# GR_Screen.net
KiCad netlist of a schematic drawn in Altium Designer
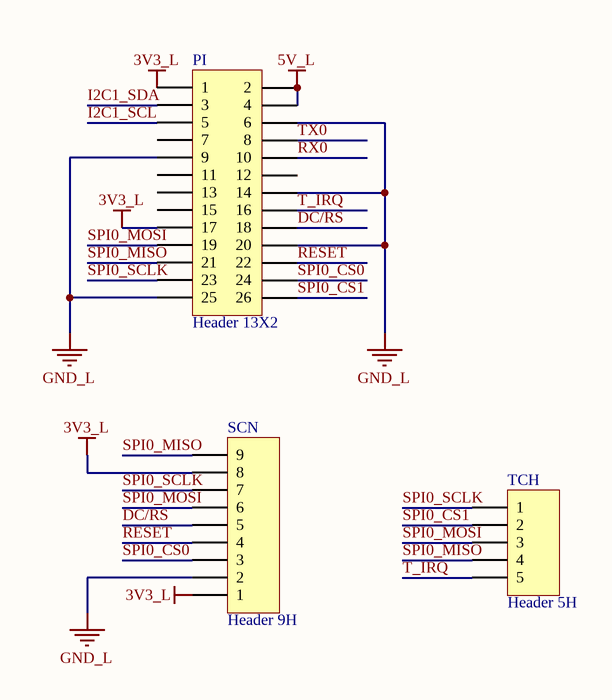
[diagram p0: GR_Screen.SchDoc]

(export (version "E")
  (design (tool "Eeschema 10.0.6"))
  (components
    (comp (ref "PI")
      (value "Header 13X2")
      (footprint "HDR2X13")
      (description "Header, 13-Pin, Dual row")
      (fields (field (name "PUBLISHER") "Altium Limited"))
      (libsource (lib "Miscellaneous Connectors") (part "Header 13X2"))
    )
    (comp (ref "SCN")
      (value "Header 9H")
      (footprint "MOLEX SPOX 9H")
      (description "Header, 9-Pin, Right Angle")
      (fields (field (name "PUBLISHER") "Altium Limited"))
      (libsource (lib "Miscellaneous Connectors") (part "Header 9H"))
    )
    (comp (ref "TCH")
      (value "Header 5H")
      (footprint "MOLEX SPOX 5H")
      (description "Header, 5-Pin, Right Angle")
      (fields (field (name "PUBLISHER") "Altium Limited"))
      (libsource (lib "Miscellaneous Connectors") (part "Header 5H"))
    )
  )
  (nets
    (net (code "1") (name "/DC{slash}RS") (class "Default")
      (node (ref "PI") (pin "18") (pinfunction "18_18") (pintype "passive"))
      (node (ref "SCN") (pin "5") (pinfunction "5_5") (pintype "passive"))
    )
    (net (code "2") (name "/I2C1_SCL") (class "Default")
      (node (ref "PI") (pin "5") (pinfunction "5_5") (pintype "passive"))
    )
    (net (code "3") (name "/I2C1_SDA") (class "Default")
      (node (ref "PI") (pin "3") (pinfunction "3_3") (pintype "passive"))
    )
    (net (code "4") (name "/RESET") (class "Default")
      (node (ref "PI") (pin "22") (pinfunction "22_22") (pintype "passive"))
      (node (ref "SCN") (pin "4") (pinfunction "4_4") (pintype "passive"))
    )
    (net (code "5") (name "/RX0") (class "Default")
      (node (ref "PI") (pin "10") (pinfunction "10_10") (pintype "passive"))
    )
    (net (code "6") (name "/SPI0_CS0") (class "Default")
      (node (ref "PI") (pin "24") (pinfunction "24_24") (pintype "passive"))
      (node (ref "SCN") (pin "3") (pinfunction "3_3") (pintype "passive"))
    )
    (net (code "7") (name "/SPI0_CS1") (class "Default")
      (node (ref "PI") (pin "26") (pinfunction "26_26") (pintype "passive"))
      (node (ref "TCH") (pin "2") (pinfunction "2_2") (pintype "passive"))
    )
    (net (code "8") (name "/SPI0_MISO") (class "Default")
      (node (ref "PI") (pin "21") (pinfunction "21_21") (pintype "passive"))
      (node (ref "SCN") (pin "9") (pinfunction "9_9") (pintype "passive"))
      (node (ref "TCH") (pin "4") (pinfunction "4_4") (pintype "passive"))
    )
    (net (code "9") (name "/SPI0_MOSI") (class "Default")
      (node (ref "PI") (pin "19") (pinfunction "19_19") (pintype "passive"))
      (node (ref "SCN") (pin "6") (pinfunction "6_6") (pintype "passive"))
      (node (ref "TCH") (pin "3") (pinfunction "3_3") (pintype "passive"))
    )
    (net (code "10") (name "/SPI0_SCLK") (class "Default")
      (node (ref "PI") (pin "23") (pinfunction "23_23") (pintype "passive"))
      (node (ref "SCN") (pin "7") (pinfunction "7_7") (pintype "passive"))
      (node (ref "TCH") (pin "1") (pinfunction "1_1") (pintype "passive"))
    )
    (net (code "11") (name "/TX0") (class "Default")
      (node (ref "PI") (pin "8") (pinfunction "8_8") (pintype "passive"))
    )
    (net (code "12") (name "/T_IRQ") (class "Default")
      (node (ref "PI") (pin "16") (pinfunction "16_16") (pintype "passive"))
      (node (ref "TCH") (pin "5") (pinfunction "5_5") (pintype "passive"))
    )
    (net (code "13") (name "3V3_L") (class "Default")
      (node (ref "PI") (pin "1") (pinfunction "1_1") (pintype "passive"))
      (node (ref "PI") (pin "17") (pinfunction "17_17") (pintype "passive"))
      (node (ref "SCN") (pin "1") (pinfunction "1_1") (pintype "passive"))
      (node (ref "SCN") (pin "8") (pinfunction "8_8") (pintype "passive"))
    )
    (net (code "14") (name "5V_L") (class "Default")
      (node (ref "PI") (pin "2") (pinfunction "2_2") (pintype "passive"))
      (node (ref "PI") (pin "4") (pinfunction "4_4") (pintype "passive"))
    )
    (net (code "15") (name "GND_L") (class "Default")
      (node (ref "PI") (pin "14") (pinfunction "14_14") (pintype "passive"))
      (node (ref "PI") (pin "20") (pinfunction "20_20") (pintype "passive"))
      (node (ref "PI") (pin "25") (pinfunction "25_25") (pintype "passive"))
      (node (ref "PI") (pin "6") (pinfunction "6_6") (pintype "passive"))
      (node (ref "PI") (pin "9") (pinfunction "9_9") (pintype "passive"))
      (node (ref "SCN") (pin "2") (pinfunction "2_2") (pintype "passive"))
    )
    (net (code "16") (name "unconnected-(PI-Pad7)") (class "Default")
      (node (ref "PI") (pin "7") (pinfunction "7_7") (pintype "passive"))
    )
    (net (code "17") (name "unconnected-(PI-Pad11)") (class "Default")
      (node (ref "PI") (pin "11") (pinfunction "11_11") (pintype "passive"))
    )
    (net (code "18") (name "unconnected-(PI-Pad12)") (class "Default")
      (node (ref "PI") (pin "12") (pinfunction "12_12") (pintype "passive"))
    )
    (net (code "19") (name "unconnected-(PI-Pad13)") (class "Default")
      (node (ref "PI") (pin "13") (pinfunction "13_13") (pintype "passive"))
    )
    (net (code "20") (name "unconnected-(PI-Pad15)") (class "Default")
      (node (ref "PI") (pin "15") (pinfunction "15_15") (pintype "passive"))
    )
  )
)
